# lin_master_node.net
KiCad netlist of a schematic drawn in EAGLE
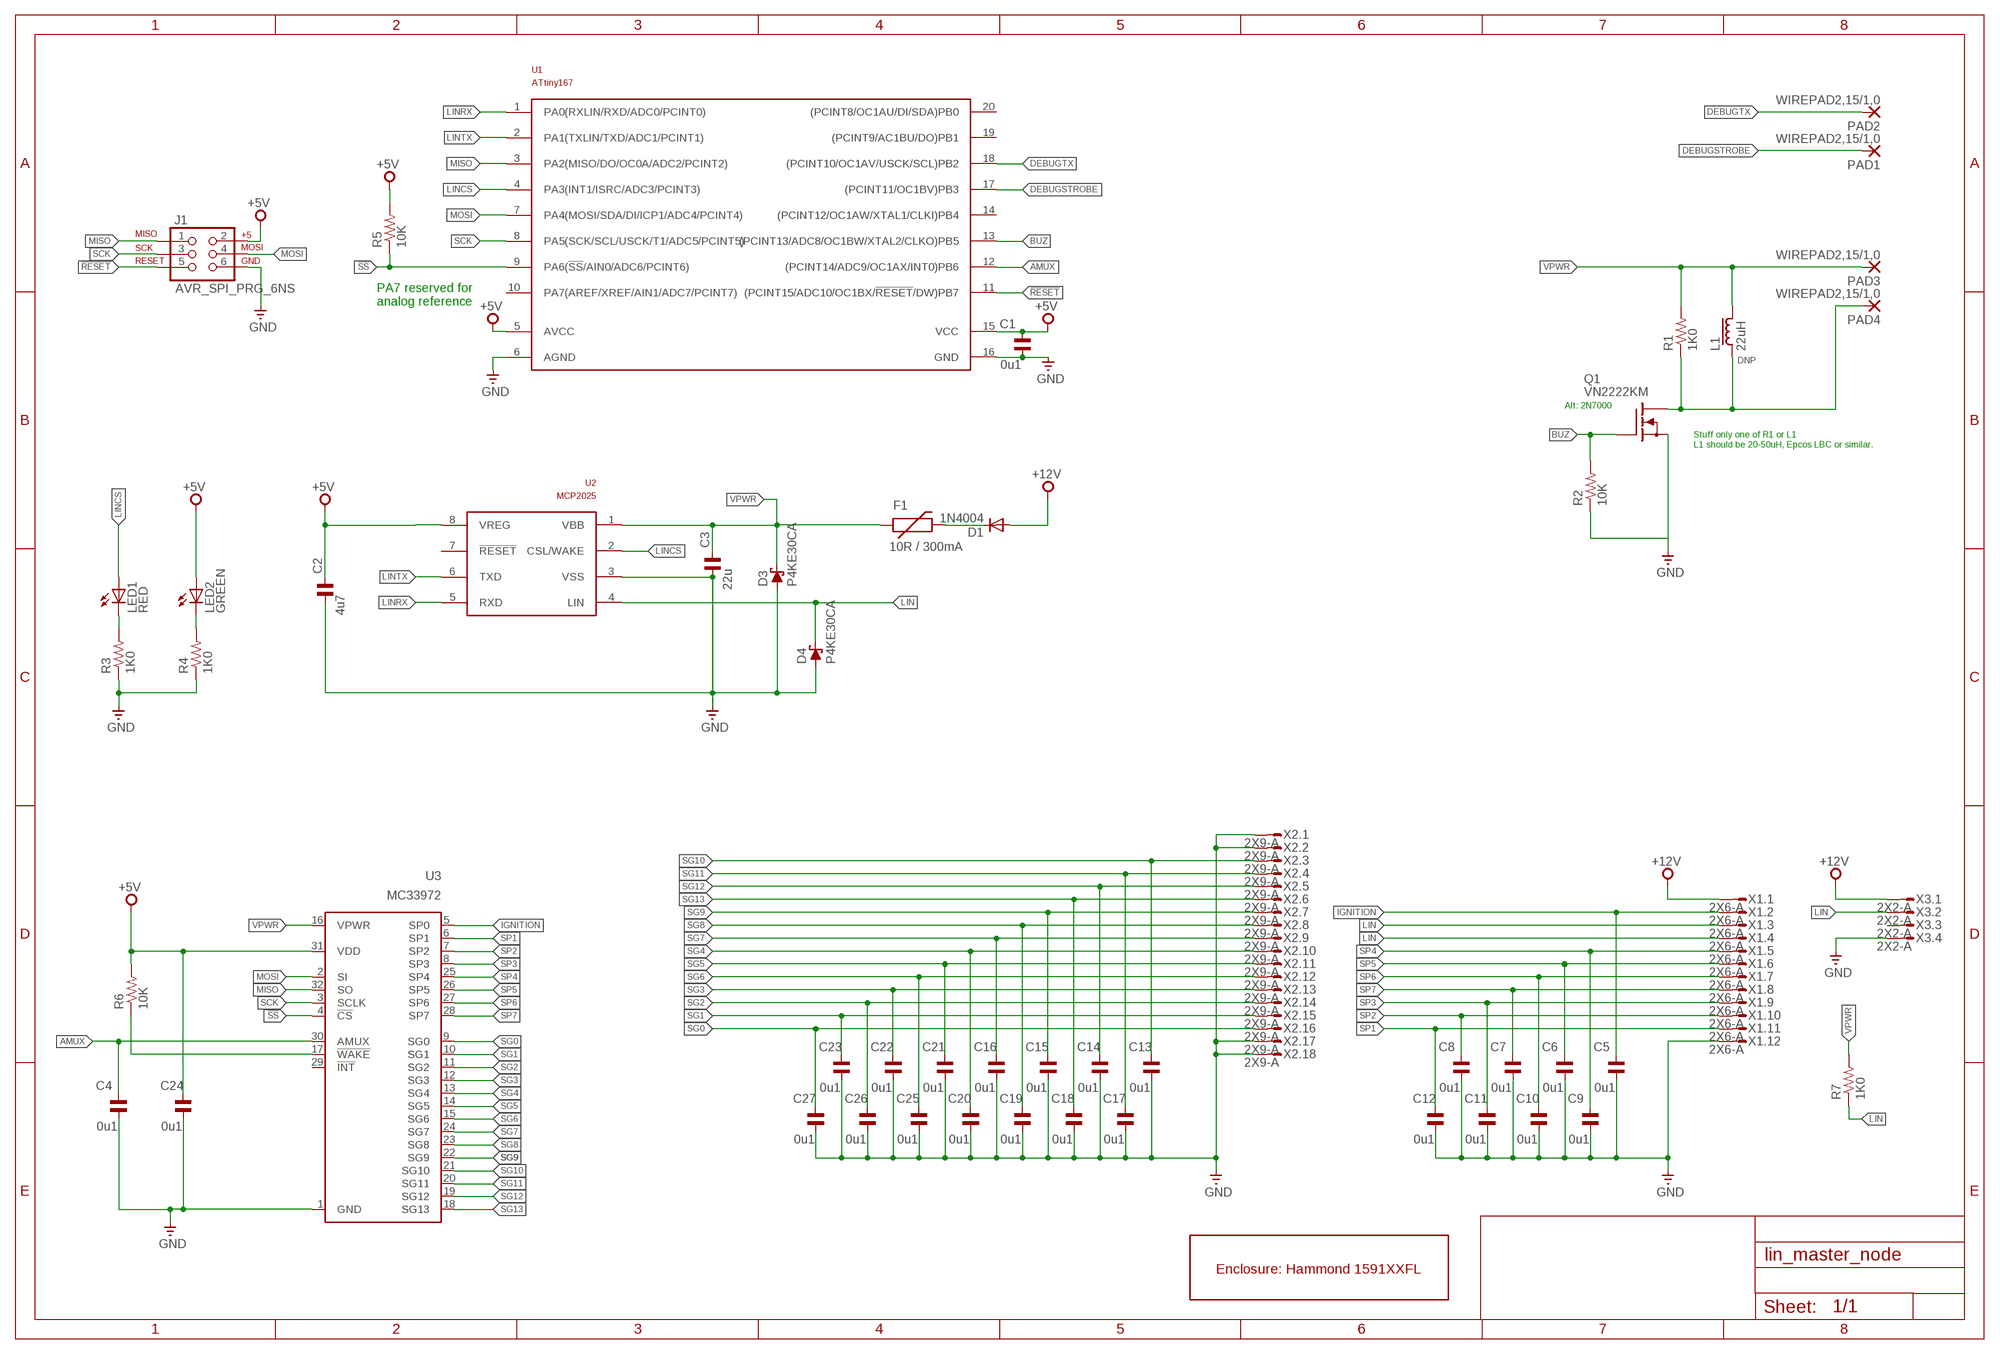
[diagram p0: schematic, sheet 1]

(export (version "E")
  (design (tool "Eeschema 10.0.6"))
  (components
    (comp (ref "C1")
      (value "0u1")
      (footprint "eagle-import:C050-024X044")
      (fields (field (name "PARTNO") "FK28X7R1H104K"))
      (libsource (lib "eagle-import") (part "C-EU050-024X044"))
    )
    (comp (ref "C2")
      (value "4u7")
      (footprint "eagle-import:C050-024X044")
      (fields (field (name "PARTNO") "FK28X5R0J475K"))
      (libsource (lib "eagle-import") (part "C-EU050-024X044"))
    )
    (comp (ref "C3")
      (value "22u")
      (footprint "eagle-import:C050-024X044")
      (fields (field (name "PARTNO") "FK22X5R1E226M"))
      (libsource (lib "eagle-import") (part "C-EU050-024X044"))
    )
    (comp (ref "C4")
      (value "0u1")
      (footprint "eagle-import:C050-024X044")
      (fields (field (name "PARTNO") "FK28X7R1H104K"))
      (libsource (lib "eagle-import") (part "C-EU050-024X044"))
    )
    (comp (ref "C5")
      (value "0u1")
      (footprint "eagle-import:C0805K")
      (fields (field (name "PARTNO") "C2012X7R1H104K085AA"))
      (libsource (lib "eagle-import") (part "C-EUC0805K"))
    )
    (comp (ref "C6")
      (value "0u1")
      (footprint "eagle-import:C0805K")
      (fields (field (name "PARTNO") "C2012X7R1H104K085AA"))
      (libsource (lib "eagle-import") (part "C-EUC0805K"))
    )
    (comp (ref "C7")
      (value "0u1")
      (footprint "eagle-import:C0805K")
      (fields (field (name "PARTNO") "C2012X7R1H104K085AA"))
      (libsource (lib "eagle-import") (part "C-EUC0805K"))
    )
    (comp (ref "C8")
      (value "0u1")
      (footprint "eagle-import:C0805K")
      (fields (field (name "PARTNO") "C2012X7R1H104K085AA"))
      (libsource (lib "eagle-import") (part "C-EUC0805K"))
    )
    (comp (ref "C9")
      (value "0u1")
      (footprint "eagle-import:C0805K")
      (fields (field (name "PARTNO") "C2012X7R1H104K085AA"))
      (libsource (lib "eagle-import") (part "C-EUC0805K"))
    )
    (comp (ref "C10")
      (value "0u1")
      (footprint "eagle-import:C0805K")
      (fields (field (name "PARTNO") "C2012X7R1H104K085AA"))
      (libsource (lib "eagle-import") (part "C-EUC0805K"))
    )
    (comp (ref "C11")
      (value "0u1")
      (footprint "eagle-import:C0805K")
      (fields (field (name "PARTNO") "C2012X7R1H104K085AA"))
      (libsource (lib "eagle-import") (part "C-EUC0805K"))
    )
    (comp (ref "C12")
      (value "0u1")
      (footprint "eagle-import:C0805K")
      (fields (field (name "PARTNO") "C2012X7R1H104K085AA"))
      (libsource (lib "eagle-import") (part "C-EUC0805K"))
    )
    (comp (ref "C13")
      (value "0u1")
      (footprint "eagle-import:C0805K")
      (fields (field (name "PARTNO") "C2012X7R1H104K085AA"))
      (libsource (lib "eagle-import") (part "C-EUC0805K"))
    )
    (comp (ref "C14")
      (value "0u1")
      (footprint "eagle-import:C0805K")
      (fields (field (name "PARTNO") "C2012X7R1H104K085AA"))
      (libsource (lib "eagle-import") (part "C-EUC0805K"))
    )
    (comp (ref "C15")
      (value "0u1")
      (footprint "eagle-import:C0805K")
      (fields (field (name "PARTNO") "C2012X7R1H104K085AA"))
      (libsource (lib "eagle-import") (part "C-EUC0805K"))
    )
    (comp (ref "C16")
      (value "0u1")
      (footprint "eagle-import:C0805K")
      (fields (field (name "PARTNO") "C2012X7R1H104K085AA"))
      (libsource (lib "eagle-import") (part "C-EUC0805K"))
    )
    (comp (ref "C17")
      (value "0u1")
      (footprint "eagle-import:C0805K")
      (fields (field (name "PARTNO") "C2012X7R1H104K085AA"))
      (libsource (lib "eagle-import") (part "C-EUC0805K"))
    )
    (comp (ref "C18")
      (value "0u1")
      (footprint "eagle-import:C0805K")
      (fields (field (name "PARTNO") "C2012X7R1H104K085AA"))
      (libsource (lib "eagle-import") (part "C-EUC0805K"))
    )
    (comp (ref "C19")
      (value "0u1")
      (footprint "eagle-import:C0805K")
      (fields (field (name "PARTNO") "C2012X7R1H104K085AA"))
      (libsource (lib "eagle-import") (part "C-EUC0805K"))
    )
    (comp (ref "C20")
      (value "0u1")
      (footprint "eagle-import:C0805K")
      (fields (field (name "PARTNO") "C2012X7R1H104K085AA"))
      (libsource (lib "eagle-import") (part "C-EUC0805K"))
    )
    (comp (ref "C21")
      (value "0u1")
      (footprint "eagle-import:C0805K")
      (fields (field (name "PARTNO") "C2012X7R1H104K085AA"))
      (libsource (lib "eagle-import") (part "C-EUC0805K"))
    )
    (comp (ref "C22")
      (value "0u1")
      (footprint "eagle-import:C0805K")
      (fields (field (name "PARTNO") "C2012X7R1H104K085AA"))
      (libsource (lib "eagle-import") (part "C-EUC0805K"))
    )
    (comp (ref "C23")
      (value "0u1")
      (footprint "eagle-import:C0805K")
      (fields (field (name "PARTNO") "C2012X7R1H104K085AA"))
      (libsource (lib "eagle-import") (part "C-EUC0805K"))
    )
    (comp (ref "C24")
      (value "0u1")
      (footprint "eagle-import:C050-024X044")
      (fields (field (name "PARTNO") "FK28X7R1H104K"))
      (libsource (lib "eagle-import") (part "C-EU050-024X044"))
    )
    (comp (ref "C25")
      (value "0u1")
      (footprint "eagle-import:C0805K")
      (fields (field (name "PARTNO") "C2012X7R1H104K085AA"))
      (libsource (lib "eagle-import") (part "C-EUC0805K"))
    )
    (comp (ref "C26")
      (value "0u1")
      (footprint "eagle-import:C0805K")
      (fields (field (name "PARTNO") "C2012X7R1H104K085AA"))
      (libsource (lib "eagle-import") (part "C-EUC0805K"))
    )
    (comp (ref "C27")
      (value "0u1")
      (footprint "eagle-import:C0805K")
      (fields (field (name "PARTNO") "C2012X7R1H104K085AA"))
      (libsource (lib "eagle-import") (part "C-EUC0805K"))
    )
    (comp (ref "D1")
      (value "1N4004")
      (footprint "eagle-import:DO41-10")
      (fields (field (name "PARTNO") "1N4004-TP"))
      (libsource (lib "eagle-import") (part "1N4004"))
    )
    (comp (ref "D3")
      (value "P4KE30CA")
      (footprint "eagle-import:DO41-10")
      (libsource (lib "eagle-import") (part "P4KEXX"))
    )
    (comp (ref "D4")
      (value "P4KE30CA")
      (footprint "eagle-import:DO41-10")
      (libsource (lib "eagle-import") (part "P4KEXX"))
    )
    (comp (ref "F1")
      (value "10R / 300mA")
      (footprint "eagle-import:PTC")
      (fields (field (name "PARTNO") "CMF-RL10-0"))
      (libsource (lib "eagle-import") (part "PTCPTH"))
    )
    (comp (ref "J1")
      (value "AVR_SPI_PRG_6NS")
      (footprint "eagle-import:2X3-NS")
      (libsource (lib "eagle-import") (part "AVR_SPI_PRG_6NS"))
    )
    (comp (ref "L1")
      (value "22uH")
      (footprint "eagle-import:LBC15A")
      (libsource (lib "eagle-import") (part "LBC15A"))
    )
    (comp (ref "LED1")
      (value "RED")
      (footprint "eagle-import:LED3MM")
      (fields (field (name "PARTNO") "C4SMF-RJS-CT0W0BB2"))
      (libsource (lib "eagle-import") (part "LED3MM"))
    )
    (comp (ref "LED2")
      (value "GREEN")
      (footprint "eagle-import:LED3MM")
      (fields (field (name "PARTNO") "C4SMF-GJS-CV0Y0792"))
      (libsource (lib "eagle-import") (part "LED3MM"))
    )
    (comp (ref "PAD1")
      (value "WIREPAD2,15/1,0")
      (footprint "eagle-import:2,15_1,0")
      (libsource (lib "eagle-import") (part "WIREPAD2,15/1,0"))
    )
    (comp (ref "PAD2")
      (value "WIREPAD2,15/1,0")
      (footprint "eagle-import:2,15_1,0")
      (libsource (lib "eagle-import") (part "WIREPAD2,15/1,0"))
    )
    (comp (ref "PAD3")
      (value "WIREPAD2,15/1,0")
      (footprint "eagle-import:2,15_1,0")
      (libsource (lib "eagle-import") (part "WIREPAD2,15/1,0"))
    )
    (comp (ref "PAD4")
      (value "WIREPAD2,15/1,0")
      (footprint "eagle-import:2,15_1,0")
      (libsource (lib "eagle-import") (part "WIREPAD2,15/1,0"))
    )
    (comp (ref "Q1")
      (value "VN2222KM")
      (footprint "eagle-import:TO237")
      (libsource (lib "eagle-import") (part "VN2222KM"))
    )
    (comp (ref "R1")
      (value "1K0")
      (footprint "eagle-import:0207_10")
      (fields (field (name "PARTNO") "CF14JT1K00"))
      (libsource (lib "eagle-import") (part "R-EU_0207/10"))
    )
    (comp (ref "R2")
      (value "10K")
      (footprint "eagle-import:0207_10")
      (fields (field (name "PARTNO") "CF14JT10K0"))
      (libsource (lib "eagle-import") (part "R-EU_0207/10"))
    )
    (comp (ref "R3")
      (value "1K0")
      (footprint "eagle-import:0207_10")
      (fields (field (name "PARTNO") "CF14JT1K00"))
      (libsource (lib "eagle-import") (part "R-EU_0207/10"))
    )
    (comp (ref "R4")
      (value "1K0")
      (footprint "eagle-import:0207_10")
      (fields (field (name "PARTNO") "CF14JT1K00"))
      (libsource (lib "eagle-import") (part "R-EU_0207/10"))
    )
    (comp (ref "R5")
      (value "10K")
      (footprint "eagle-import:0207_10")
      (fields (field (name "PARTNO") "CF14JT10K0"))
      (libsource (lib "eagle-import") (part "R-EU_0207/10"))
    )
    (comp (ref "R6")
      (value "10K")
      (footprint "eagle-import:0207_10")
      (fields (field (name "PARTNO") "CF14JT10K0"))
      (libsource (lib "eagle-import") (part "R-EU_0207/10"))
    )
    (comp (ref "R7")
      (value "1K0")
      (footprint "eagle-import:0207_10")
      (fields (field (name "PARTNO") "CF14JT1K00"))
      (libsource (lib "eagle-import") (part "R-EU_0207/10"))
    )
    (comp (ref "U$1")
      (value "1591XXAFL")
      (footprint "eagle-import:1591XXAFL")
      (fields (field (name "PARTNO") "1591XXAFLBK"))
      (libsource (lib "eagle-import") (part "1591XXAFL"))
    )
    (comp (ref "U1")
      (value "ATtiny167")
      (footprint "eagle-import:SO20W")
      (fields (field (name "PARTNO") "ATTINY167-SU"))
      (libsource (lib "eagle-import") (part "ATTINY167"))
    )
    (comp (ref "U2")
      (value "MCP2025")
      (footprint "eagle-import:SO08")
      (fields (field (name "PARTNO") "MCP2025-500E/SN"))
      (libsource (lib "eagle-import") (part "MCP2025"))
    )
    (comp (ref "U3")
      (value "MC33972")
      (footprint "eagle-import:SOIC32W")
      (fields (field (name "PARTNO") "MC33972ATEW"))
      (libsource (lib "eagle-import") (part "MC33972"))
    )
    (comp (ref "X1")
      (value "2X6-A")
      (footprint "eagle-import:4-794618-2")
      (fields (field (name "PARTNO") "4-794618-2"))
      (libsource (lib "eagle-import") (part "2X6-A"))
    )
    (comp (ref "X2")
      (value "2X9-A")
      (footprint "eagle-import:4-794618-8")
      (fields (field (name "PARTNO") "4-794618-8"))
      (libsource (lib "eagle-import") (part "2X9-A"))
    )
    (comp (ref "X3")
      (value "2X2-A")
      (footprint "eagle-import:3-794618-4")
      (fields (field (name "PARTNO") "3-794618-4"))
      (libsource (lib "eagle-import") (part "2X2-A"))
    )
  )
  (nets
    (net (code "1") (name "+5V") (class "Default")
      (node (ref "C1") (pin "1") (pinfunction "1_1") (pintype "passive"))
      (node (ref "C2") (pin "1") (pinfunction "1_1") (pintype "passive"))
      (node (ref "C24") (pin "1") (pinfunction "1_1") (pintype "passive"))
      (node (ref "J1") (pin "2") (pinfunction "2_2") (pintype "passive"))
      (node (ref "LED2") (pin "A") (pinfunction "A_A") (pintype "passive"))
      (node (ref "R5") (pin "2") (pinfunction "2_2") (pintype "passive"))
      (node (ref "R6") (pin "2") (pinfunction "2_2") (pintype "passive"))
      (node (ref "U1") (pin "15") (pinfunction "VCC_15") (pintype "power_in"))
      (node (ref "U1") (pin "5") (pinfunction "AVCC_5") (pintype "power_in"))
      (node (ref "U2") (pin "8") (pinfunction "VREG_8") (pintype "power_in"))
      (node (ref "U3") (pin "31") (pinfunction "VDD_31") (pintype "power_in"))
    )
    (net (code "2") (name "+12V") (class "Default")
      (node (ref "D1") (pin "A") (pinfunction "A_A") (pintype "passive"))
      (node (ref "X1") (pin "1") (pinfunction "S_1") (pintype "passive"))
      (node (ref "X3") (pin "1") (pinfunction "S_1") (pintype "passive"))
    )
    (net (code "3") (name "/~{RESET}") (class "Default")
      (node (ref "J1") (pin "5") (pinfunction "5_5") (pintype "passive"))
      (node (ref "U1") (pin "11") (pinfunction "(PCINT15/ADC10/OC1BX/~{RESET}/DW)PB7_11") (pintype "bidirectional"))
    )
    (net (code "4") (name "/~{SS}") (class "Default")
      (node (ref "R5") (pin "1") (pinfunction "1_1") (pintype "passive"))
      (node (ref "U1") (pin "9") (pinfunction "PA6(~{SS}/AIN0/ADC6/PCINT6)_9") (pintype "bidirectional"))
      (node (ref "U3") (pin "4") (pinfunction "~{CS}_4") (pintype "input"))
    )
    (net (code "5") (name "AMUX") (class "Default")
      (node (ref "C4") (pin "1") (pinfunction "1_1") (pintype "passive"))
      (node (ref "U1") (pin "12") (pinfunction "(PCINT14/ADC9/OC1AX/INT0)PB6_12") (pintype "bidirectional"))
      (node (ref "U3") (pin "30") (pinfunction "AMUX_30") (pintype "output"))
    )
    (net (code "6") (name "BUZ") (class "Default")
      (node (ref "Q1") (pin "2") (pinfunction "G_2") (pintype "passive"))
      (node (ref "R2") (pin "2") (pinfunction "2_2") (pintype "passive"))
      (node (ref "U1") (pin "13") (pinfunction "(PCINT13/ADC8/OC1BW/XTAL2/CLKO)PB5_13") (pintype "bidirectional"))
    )
    (net (code "7") (name "DEBUGSTROBE") (class "Default")
      (node (ref "PAD1") (pin "1") (pinfunction "P_1") (pintype "passive"))
      (node (ref "U1") (pin "17") (pinfunction "(PCINT11/OC1BV)PB3_17") (pintype "bidirectional"))
    )
    (net (code "8") (name "DEBUGTX") (class "Default")
      (node (ref "PAD2") (pin "1") (pinfunction "P_1") (pintype "passive"))
      (node (ref "U1") (pin "18") (pinfunction "(PCINT10/OC1AV/USCK/SCL)PB2_18") (pintype "bidirectional"))
    )
    (net (code "9") (name "GND") (class "Default")
      (node (ref "C1") (pin "2") (pinfunction "2_2") (pintype "passive"))
      (node (ref "C10") (pin "2") (pinfunction "2_2") (pintype "passive"))
      (node (ref "C11") (pin "2") (pinfunction "2_2") (pintype "passive"))
      (node (ref "C12") (pin "2") (pinfunction "2_2") (pintype "passive"))
      (node (ref "C13") (pin "2") (pinfunction "2_2") (pintype "passive"))
      (node (ref "C14") (pin "2") (pinfunction "2_2") (pintype "passive"))
      (node (ref "C15") (pin "2") (pinfunction "2_2") (pintype "passive"))
      (node (ref "C16") (pin "2") (pinfunction "2_2") (pintype "passive"))
      (node (ref "C17") (pin "2") (pinfunction "2_2") (pintype "passive"))
      (node (ref "C18") (pin "2") (pinfunction "2_2") (pintype "passive"))
      (node (ref "C19") (pin "2") (pinfunction "2_2") (pintype "passive"))
      (node (ref "C2") (pin "2") (pinfunction "2_2") (pintype "passive"))
      (node (ref "C20") (pin "2") (pinfunction "2_2") (pintype "passive"))
      (node (ref "C21") (pin "2") (pinfunction "2_2") (pintype "passive"))
      (node (ref "C22") (pin "2") (pinfunction "2_2") (pintype "passive"))
      (node (ref "C23") (pin "2") (pinfunction "2_2") (pintype "passive"))
      (node (ref "C24") (pin "2") (pinfunction "2_2") (pintype "passive"))
      (node (ref "C25") (pin "2") (pinfunction "2_2") (pintype "passive"))
      (node (ref "C26") (pin "2") (pinfunction "2_2") (pintype "passive"))
      (node (ref "C27") (pin "2") (pinfunction "2_2") (pintype "passive"))
      (node (ref "C3") (pin "2") (pinfunction "2_2") (pintype "passive"))
      (node (ref "C4") (pin "2") (pinfunction "2_2") (pintype "passive"))
      (node (ref "C5") (pin "2") (pinfunction "2_2") (pintype "passive"))
      (node (ref "C6") (pin "2") (pinfunction "2_2") (pintype "passive"))
      (node (ref "C7") (pin "2") (pinfunction "2_2") (pintype "passive"))
      (node (ref "C8") (pin "2") (pinfunction "2_2") (pintype "passive"))
      (node (ref "C9") (pin "2") (pinfunction "2_2") (pintype "passive"))
      (node (ref "D3") (pin "A") (pinfunction "A_A") (pintype "passive"))
      (node (ref "D4") (pin "A") (pinfunction "A_A") (pintype "passive"))
      (node (ref "J1") (pin "6") (pinfunction "6_6") (pintype "passive"))
      (node (ref "Q1") (pin "3") (pinfunction "S_3") (pintype "passive"))
      (node (ref "R2") (pin "1") (pinfunction "1_1") (pintype "passive"))
      (node (ref "R3") (pin "1") (pinfunction "1_1") (pintype "passive"))
      (node (ref "R4") (pin "1") (pinfunction "1_1") (pintype "passive"))
      (node (ref "U1") (pin "16") (pinfunction "GND_16") (pintype "power_in"))
      (node (ref "U1") (pin "6") (pinfunction "AGND_6") (pintype "power_in"))
      (node (ref "U2") (pin "3") (pinfunction "VSS_3") (pintype "power_in"))
      (node (ref "U3") (pin "1") (pinfunction "GND_1") (pintype "power_in"))
      (node (ref "X1") (pin "12") (pinfunction "S_12") (pintype "passive"))
      (node (ref "X2") (pin "1") (pinfunction "S_1") (pintype "passive"))
      (node (ref "X2") (pin "17") (pinfunction "S_17") (pintype "passive"))
      (node (ref "X2") (pin "18") (pinfunction "S_18") (pintype "passive"))
      (node (ref "X2") (pin "2") (pinfunction "S_2") (pintype "passive"))
      (node (ref "X3") (pin "4") (pinfunction "S_4") (pintype "passive"))
    )
    (net (code "10") (name "IGNITION") (class "Default")
      (node (ref "C5") (pin "1") (pinfunction "1_1") (pintype "passive"))
      (node (ref "U3") (pin "5") (pinfunction "SP0_5") (pintype "input"))
      (node (ref "X1") (pin "2") (pinfunction "S_2") (pintype "passive"))
    )
    (net (code "11") (name "LIN") (class "Default")
      (node (ref "D4") (pin "C") (pinfunction "C_C") (pintype "passive"))
      (node (ref "R7") (pin "1") (pinfunction "1_1") (pintype "passive"))
      (node (ref "U2") (pin "4") (pinfunction "LIN_4") (pintype "bidirectional"))
      (node (ref "X1") (pin "3") (pinfunction "S_3") (pintype "passive"))
      (node (ref "X1") (pin "4") (pinfunction "S_4") (pintype "passive"))
      (node (ref "X3") (pin "2") (pinfunction "S_2") (pintype "passive"))
    )
    (net (code "12") (name "LINCS") (class "Default")
      (node (ref "LED1") (pin "A") (pinfunction "A_A") (pintype "passive"))
      (node (ref "U1") (pin "4") (pinfunction "PA3(INT1/ISRC/ADC3/PCINT3)_4") (pintype "bidirectional"))
      (node (ref "U2") (pin "2") (pinfunction "CSL/WAKE_2") (pintype "input"))
    )
    (net (code "13") (name "LINRX") (class "Default")
      (node (ref "U1") (pin "1") (pinfunction "PA0(RXLIN/RXD/ADC0/PCINT0)_1") (pintype "bidirectional"))
      (node (ref "U2") (pin "5") (pinfunction "RXD_5") (pintype "output"))
    )
    (net (code "14") (name "LINTX") (class "Default")
      (node (ref "U1") (pin "2") (pinfunction "PA1(TXLIN/TXD/ADC1/PCINT1)_2") (pintype "bidirectional"))
      (node (ref "U2") (pin "6") (pinfunction "TXD_6") (pintype "input"))
    )
    (net (code "15") (name "MISO") (class "Default")
      (node (ref "J1") (pin "1") (pinfunction "1_1") (pintype "passive"))
      (node (ref "U1") (pin "3") (pinfunction "PA2(MISO/DO/OC0A/ADC2/PCINT2)_3") (pintype "bidirectional"))
      (node (ref "U3") (pin "32") (pinfunction "SO_32") (pintype "output"))
    )
    (net (code "16") (name "MOSI") (class "Default")
      (node (ref "J1") (pin "4") (pinfunction "4_4") (pintype "passive"))
      (node (ref "U1") (pin "7") (pinfunction "PA4(MOSI/SDA/DI/ICP1/ADC4/PCINT4)_7") (pintype "bidirectional"))
      (node (ref "U3") (pin "2") (pinfunction "SI_2") (pintype "input"))
    )
    (net (code "17") (name "Net-(F1-2)") (class "Default")
      (node (ref "D1") (pin "C") (pinfunction "C_C") (pintype "passive"))
      (node (ref "F1") (pin "P$2") (pinfunction "2_P$2") (pintype "bidirectional"))
    )
    (net (code "18") (name "Net-(LED1-C)") (class "Default")
      (node (ref "LED1") (pin "K") (pinfunction "C_K") (pintype "passive"))
      (node (ref "R3") (pin "2") (pinfunction "2_2") (pintype "passive"))
    )
    (net (code "19") (name "Net-(LED2-C)") (class "Default")
      (node (ref "LED2") (pin "K") (pinfunction "C_K") (pintype "passive"))
      (node (ref "R4") (pin "2") (pinfunction "2_2") (pintype "passive"))
    )
    (net (code "20") (name "Net-(PAD4-P)") (class "Default")
      (node (ref "L1") (pin "1") (pinfunction "1_1") (pintype "passive"))
      (node (ref "PAD4") (pin "1") (pinfunction "P_1") (pintype "passive"))
      (node (ref "Q1") (pin "1") (pinfunction "D_1") (pintype "passive"))
      (node (ref "R1") (pin "1") (pinfunction "1_1") (pintype "passive"))
    )
    (net (code "21") (name "Net-(U3-~{WAKE})") (class "Default")
      (node (ref "R6") (pin "1") (pinfunction "1_1") (pintype "passive"))
      (node (ref "U3") (pin "17") (pinfunction "~{WAKE}_17") (pintype "open_collector"))
    )
    (net (code "22") (name "SCK") (class "Default")
      (node (ref "J1") (pin "3") (pinfunction "3_3") (pintype "passive"))
      (node (ref "U1") (pin "8") (pinfunction "PA5(SCK/SCL/USCK/T1/ADC5/PCINT5)_8") (pintype "bidirectional"))
      (node (ref "U3") (pin "3") (pinfunction "SCLK_3") (pintype "input"))
    )
    (net (code "23") (name "SG0") (class "Default")
      (node (ref "C27") (pin "1") (pinfunction "1_1") (pintype "passive"))
      (node (ref "U3") (pin "9") (pinfunction "SG0_9") (pintype "input"))
      (node (ref "X2") (pin "16") (pinfunction "S_16") (pintype "passive"))
    )
    (net (code "24") (name "SG1") (class "Default")
      (node (ref "C23") (pin "1") (pinfunction "1_1") (pintype "passive"))
      (node (ref "U3") (pin "10") (pinfunction "SG1_10") (pintype "input"))
      (node (ref "X2") (pin "15") (pinfunction "S_15") (pintype "passive"))
    )
    (net (code "25") (name "SG2") (class "Default")
      (node (ref "C26") (pin "1") (pinfunction "1_1") (pintype "passive"))
      (node (ref "U3") (pin "11") (pinfunction "SG2_11") (pintype "input"))
      (node (ref "X2") (pin "14") (pinfunction "S_14") (pintype "passive"))
    )
    (net (code "26") (name "SG3") (class "Default")
      (node (ref "C22") (pin "1") (pinfunction "1_1") (pintype "passive"))
      (node (ref "U3") (pin "12") (pinfunction "SG3_12") (pintype "input"))
      (node (ref "X2") (pin "13") (pinfunction "S_13") (pintype "passive"))
    )
    (net (code "27") (name "SG4") (class "Default")
      (node (ref "C20") (pin "1") (pinfunction "1_1") (pintype "passive"))
      (node (ref "U3") (pin "13") (pinfunction "SG4_13") (pintype "input"))
      (node (ref "X2") (pin "10") (pinfunction "S_10") (pintype "passive"))
    )
    (net (code "28") (name "SG5") (class "Default")
      (node (ref "C21") (pin "1") (pinfunction "1_1") (pintype "passive"))
      (node (ref "U3") (pin "14") (pinfunction "SG5_14") (pintype "input"))
      (node (ref "X2") (pin "11") (pinfunction "S_11") (pintype "passive"))
    )
    (net (code "29") (name "SG6") (class "Default")
      (node (ref "C25") (pin "1") (pinfunction "1_1") (pintype "passive"))
      (node (ref "U3") (pin "15") (pinfunction "SG6_15") (pintype "input"))
      (node (ref "X2") (pin "12") (pinfunction "S_12") (pintype "passive"))
    )
    (net (code "30") (name "SG7") (class "Default")
      (node (ref "C16") (pin "1") (pinfunction "1_1") (pintype "passive"))
      (node (ref "U3") (pin "24") (pinfunction "SG7_24") (pintype "input"))
      (node (ref "X2") (pin "9") (pinfunction "S_9") (pintype "passive"))
    )
    (net (code "31") (name "SG8") (class "Default")
      (node (ref "C19") (pin "1") (pinfunction "1_1") (pintype "passive"))
      (node (ref "U3") (pin "23") (pinfunction "SG8_23") (pintype "input"))
      (node (ref "X2") (pin "8") (pinfunction "S_8") (pintype "passive"))
    )
    (net (code "32") (name "SG9") (class "Default")
      (node (ref "C15") (pin "1") (pinfunction "1_1") (pintype "passive"))
      (node (ref "U3") (pin "22") (pinfunction "SG9_22") (pintype "input"))
      (node (ref "X2") (pin "7") (pinfunction "S_7") (pintype "passive"))
    )
    (net (code "33") (name "SG10") (class "Default")
      (node (ref "C13") (pin "1") (pinfunction "1_1") (pintype "passive"))
      (node (ref "U3") (pin "21") (pinfunction "SG10_21") (pintype "input"))
      (node (ref "X2") (pin "3") (pinfunction "S_3") (pintype "passive"))
    )
    (net (code "34") (name "SG11") (class "Default")
      (node (ref "C17") (pin "1") (pinfunction "1_1") (pintype "passive"))
      (node (ref "U3") (pin "20") (pinfunction "SG11_20") (pintype "input"))
      (node (ref "X2") (pin "4") (pinfunction "S_4") (pintype "passive"))
    )
    (net (code "35") (name "SG12") (class "Default")
      (node (ref "C14") (pin "1") (pinfunction "1_1") (pintype "passive"))
      (node (ref "U3") (pin "19") (pinfunction "SG12_19") (pintype "input"))
      (node (ref "X2") (pin "5") (pinfunction "S_5") (pintype "passive"))
    )
    (net (code "36") (name "SG13") (class "Default")
      (node (ref "C18") (pin "1") (pinfunction "1_1") (pintype "passive"))
      (node (ref "U3") (pin "18") (pinfunction "SG13_18") (pintype "input"))
      (node (ref "X2") (pin "6") (pinfunction "S_6") (pintype "passive"))
    )
    (net (code "37") (name "SP1") (class "Default")
      (node (ref "C12") (pin "1") (pinfunction "1_1") (pintype "passive"))
      (node (ref "U3") (pin "6") (pinfunction "SP1_6") (pintype "input"))
      (node (ref "X1") (pin "11") (pinfunction "S_11") (pintype "passive"))
    )
    (net (code "38") (name "SP2") (class "Default")
      (node (ref "C8") (pin "1") (pinfunction "1_1") (pintype "passive"))
      (node (ref "U3") (pin "7") (pinfunction "SP2_7") (pintype "input"))
      (node (ref "X1") (pin "10") (pinfunction "S_10") (pintype "passive"))
    )
    (net (code "39") (name "SP3") (class "Default")
      (node (ref "C11") (pin "1") (pinfunction "1_1") (pintype "passive"))
      (node (ref "U3") (pin "8") (pinfunction "SP3_8") (pintype "input"))
      (node (ref "X1") (pin "9") (pinfunction "S_9") (pintype "passive"))
    )
    (net (code "40") (name "SP4") (class "Default")
      (node (ref "C9") (pin "1") (pinfunction "1_1") (pintype "passive"))
      (node (ref "U3") (pin "25") (pinfunction "SP4_25") (pintype "input"))
      (node (ref "X1") (pin "5") (pinfunction "S_5") (pintype "passive"))
    )
    (net (code "41") (name "SP5") (class "Default")
      (node (ref "C6") (pin "1") (pinfunction "1_1") (pintype "passive"))
      (node (ref "U3") (pin "26") (pinfunction "SP5_26") (pintype "input"))
      (node (ref "X1") (pin "6") (pinfunction "S_6") (pintype "passive"))
    )
    (net (code "42") (name "SP6") (class "Default")
      (node (ref "C10") (pin "1") (pinfunction "1_1") (pintype "passive"))
      (node (ref "U3") (pin "27") (pinfunction "SP6_27") (pintype "input"))
      (node (ref "X1") (pin "7") (pinfunction "S_7") (pintype "passive"))
    )
    (net (code "43") (name "SP7") (class "Default")
      (node (ref "C7") (pin "1") (pinfunction "1_1") (pintype "passive"))
      (node (ref "U3") (pin "28") (pinfunction "SP7_28") (pintype "input"))
      (node (ref "X1") (pin "8") (pinfunction "S_8") (pintype "passive"))
    )
    (net (code "44") (name "VPWR") (class "Default")
      (node (ref "C3") (pin "1") (pinfunction "1_1") (pintype "passive"))
      (node (ref "D3") (pin "C") (pinfunction "C_C") (pintype "passive"))
      (node (ref "F1") (pin "P$1") (pinfunction "1_P$1") (pintype "bidirectional"))
      (node (ref "L1") (pin "2") (pinfunction "2_2") (pintype "passive"))
      (node (ref "PAD3") (pin "1") (pinfunction "P_1") (pintype "passive"))
      (node (ref "R1") (pin "2") (pinfunction "2_2") (pintype "passive"))
      (node (ref "R7") (pin "2") (pinfunction "2_2") (pintype "passive"))
      (node (ref "U2") (pin "1") (pinfunction "VBB_1") (pintype "power_in"))
      (node (ref "U3") (pin "16") (pinfunction "VPWR_16") (pintype "power_in"))
    )
    (net (code "45") (name "unconnected-(U1-(PCINT8{slash}OC1AU{slash}DI{slash}SDA)PB0-Pad20)") (class "Default")
      (node (ref "U1") (pin "20") (pinfunction "(PCINT8/OC1AU/DI/SDA)PB0_20") (pintype "bidirectional"))
    )
    (net (code "46") (name "unconnected-(U1-(PCINT9{slash}AC1BU{slash}DO)PB1-Pad19)") (class "Default")
      (node (ref "U1") (pin "19") (pinfunction "(PCINT9/AC1BU/DO)PB1_19") (pintype "bidirectional"))
    )
    (net (code "47") (name "unconnected-(U1-(PCINT12{slash}OC1AW{slash}XTAL1{slash}CLKI)PB4-Pad14)") (class "Default")
      (node (ref "U1") (pin "14") (pinfunction "(PCINT12/OC1AW/XTAL1/CLKI)PB4_14") (pintype "bidirectional"))
    )
    (net (code "48") (name "unconnected-(U1-PA7(AREF{slash}XREF{slash}AIN1{slash}ADC7{slash}PCINT7)-Pad10)") (class "Default")
      (node (ref "U1") (pin "10") (pinfunction "PA7(AREF/XREF/AIN1/ADC7/PCINT7)_10") (pintype "bidirectional"))
    )
    (net (code "49") (name "unconnected-(U2-~{RESET}-Pad7)") (class "Default")
      (node (ref "U2") (pin "7") (pinfunction "~{RESET}_7") (pintype "open_collector"))
    )
    (net (code "50") (name "unconnected-(U3-~{INT}-Pad29)") (class "Default")
      (node (ref "U3") (pin "29") (pinfunction "~{INT}_29") (pintype "open_collector"))
    )
    (net (code "51") (name "unconnected-(X3C-S-Pad3)") (class "Default")
      (node (ref "X3") (pin "3") (pinfunction "S_3") (pintype "passive"))
    )
  )
)
